# led_and_button.net
KiCad netlist of a schematic drawn in Altium Designer
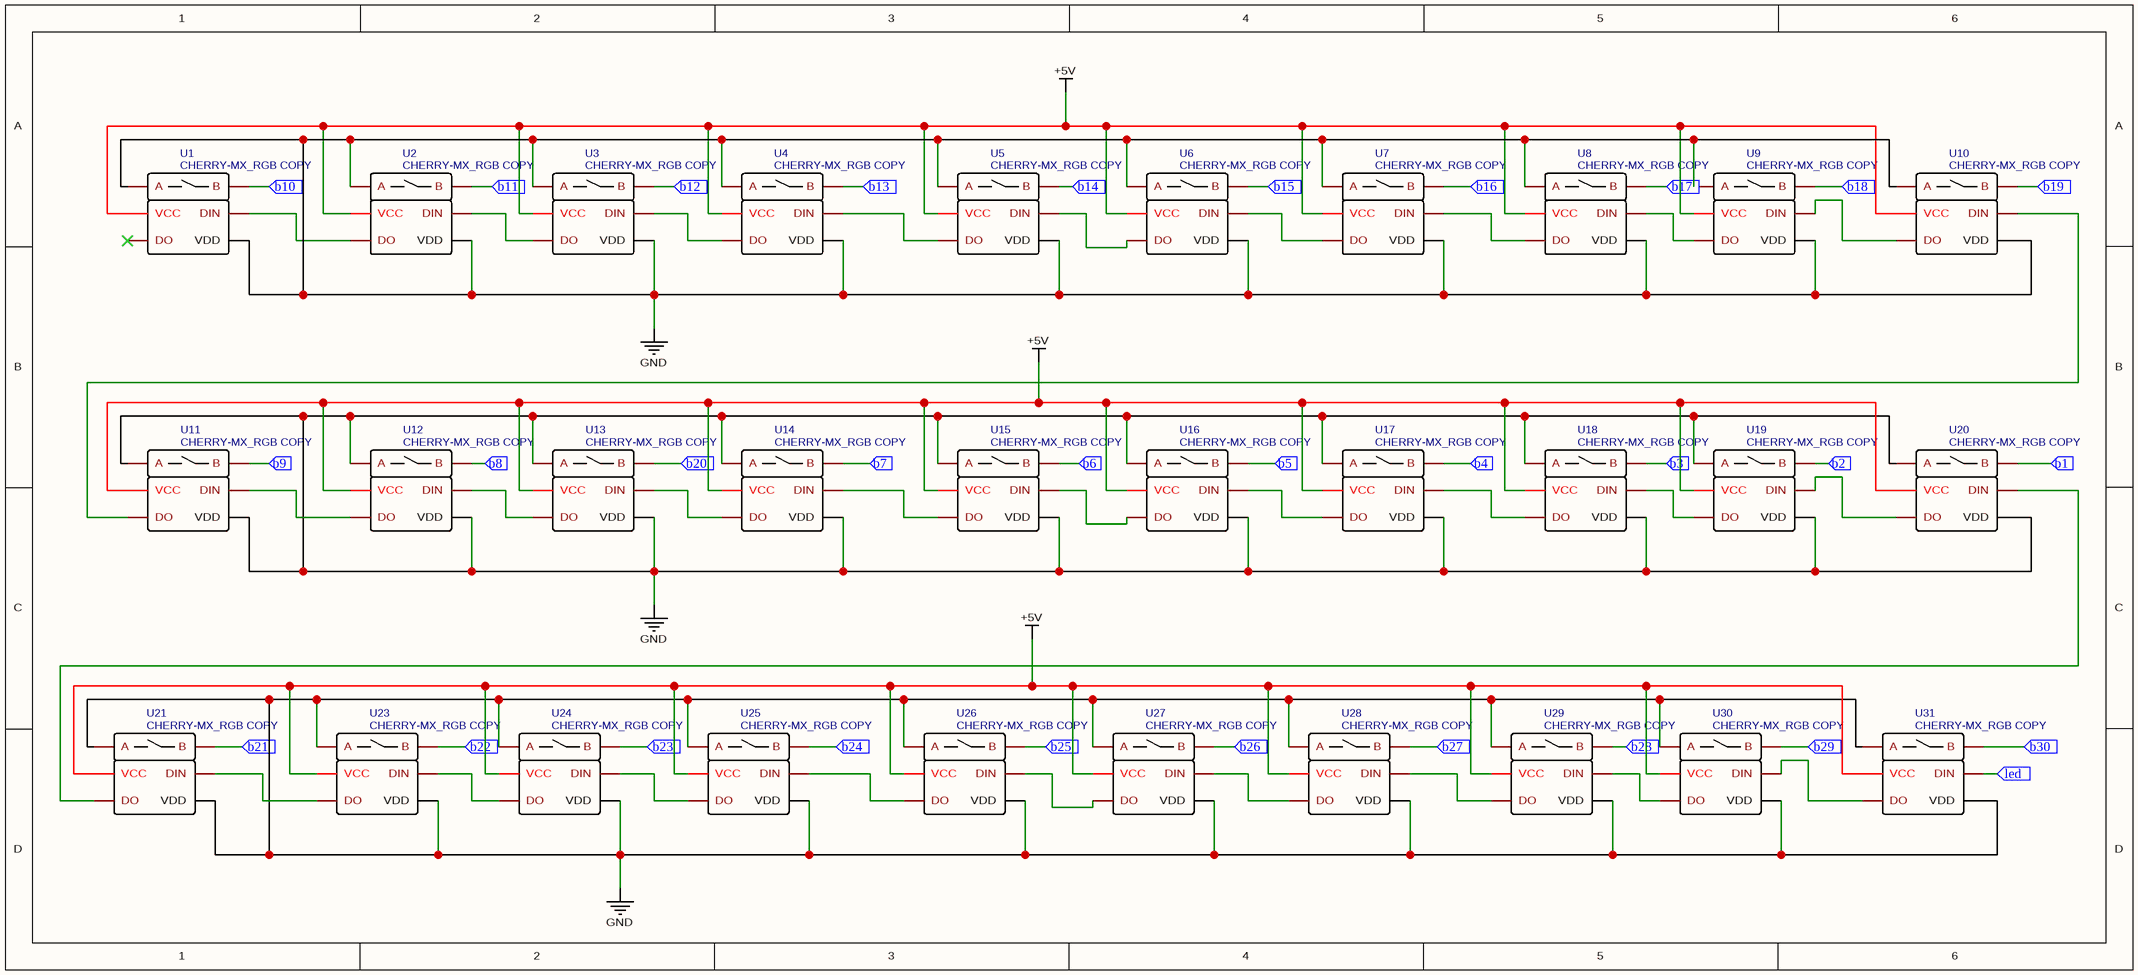
[diagram p0: led and button.schdoc]

(export (version "E")
  (design (tool "Eeschema 10.0.6"))
  (components
    (comp (ref "U1")
      (value "CHERRY-MX_RGB COPY")
      (fields (field (name "CONTRIBUTOR") "unrealin01"))
      (libsource (lib "altium-import") (part "root_0_CHERRY-MX_RGB COPY_"))
    )
    (comp (ref "U2")
      (value "CHERRY-MX_RGB COPY")
      (fields (field (name "CONTRIBUTOR") "unrealin01"))
      (libsource (lib "altium-import") (part "root_0_CHERRY-MX_RGB COPY_"))
    )
    (comp (ref "U3")
      (value "CHERRY-MX_RGB COPY")
      (fields (field (name "CONTRIBUTOR") "unrealin01"))
      (libsource (lib "altium-import") (part "root_0_CHERRY-MX_RGB COPY_"))
    )
    (comp (ref "U4")
      (value "CHERRY-MX_RGB COPY")
      (fields (field (name "CONTRIBUTOR") "unrealin01"))
      (libsource (lib "altium-import") (part "root_0_CHERRY-MX_RGB COPY_"))
    )
    (comp (ref "U5")
      (value "CHERRY-MX_RGB COPY")
      (fields (field (name "CONTRIBUTOR") "unrealin01"))
      (libsource (lib "altium-import") (part "root_0_CHERRY-MX_RGB COPY_"))
    )
    (comp (ref "U6")
      (value "CHERRY-MX_RGB COPY")
      (fields (field (name "CONTRIBUTOR") "unrealin01"))
      (libsource (lib "altium-import") (part "root_0_CHERRY-MX_RGB COPY_"))
    )
    (comp (ref "U7")
      (value "CHERRY-MX_RGB COPY")
      (fields (field (name "CONTRIBUTOR") "unrealin01"))
      (libsource (lib "altium-import") (part "root_0_CHERRY-MX_RGB COPY_"))
    )
    (comp (ref "U8")
      (value "CHERRY-MX_RGB COPY")
      (fields (field (name "CONTRIBUTOR") "unrealin01"))
      (libsource (lib "altium-import") (part "root_0_CHERRY-MX_RGB COPY_"))
    )
    (comp (ref "U9")
      (value "CHERRY-MX_RGB COPY")
      (fields (field (name "CONTRIBUTOR") "unrealin01"))
      (libsource (lib "altium-import") (part "root_0_CHERRY-MX_RGB COPY_"))
    )
    (comp (ref "U10")
      (value "CHERRY-MX_RGB COPY")
      (fields (field (name "CONTRIBUTOR") "unrealin01"))
      (libsource (lib "altium-import") (part "root_0_CHERRY-MX_RGB COPY_"))
    )
    (comp (ref "U11")
      (value "CHERRY-MX_RGB COPY")
      (fields (field (name "CONTRIBUTOR") "unrealin01"))
      (libsource (lib "altium-import") (part "root_0_CHERRY-MX_RGB COPY_"))
    )
    (comp (ref "U12")
      (value "CHERRY-MX_RGB COPY")
      (fields (field (name "CONTRIBUTOR") "unrealin01"))
      (libsource (lib "altium-import") (part "root_0_CHERRY-MX_RGB COPY_"))
    )
    (comp (ref "U13")
      (value "CHERRY-MX_RGB COPY")
      (fields (field (name "CONTRIBUTOR") "unrealin01"))
      (libsource (lib "altium-import") (part "root_0_CHERRY-MX_RGB COPY_"))
    )
    (comp (ref "U14")
      (value "CHERRY-MX_RGB COPY")
      (fields (field (name "CONTRIBUTOR") "unrealin01"))
      (libsource (lib "altium-import") (part "root_0_CHERRY-MX_RGB COPY_"))
    )
    (comp (ref "U15")
      (value "CHERRY-MX_RGB COPY")
      (fields (field (name "CONTRIBUTOR") "unrealin01"))
      (libsource (lib "altium-import") (part "root_0_CHERRY-MX_RGB COPY_"))
    )
    (comp (ref "U16")
      (value "CHERRY-MX_RGB COPY")
      (fields (field (name "CONTRIBUTOR") "unrealin01"))
      (libsource (lib "altium-import") (part "root_0_CHERRY-MX_RGB COPY_"))
    )
    (comp (ref "U17")
      (value "CHERRY-MX_RGB COPY")
      (fields (field (name "CONTRIBUTOR") "unrealin01"))
      (libsource (lib "altium-import") (part "root_0_CHERRY-MX_RGB COPY_"))
    )
    (comp (ref "U18")
      (value "CHERRY-MX_RGB COPY")
      (fields (field (name "CONTRIBUTOR") "unrealin01"))
      (libsource (lib "altium-import") (part "root_0_CHERRY-MX_RGB COPY_"))
    )
    (comp (ref "U19")
      (value "CHERRY-MX_RGB COPY")
      (fields (field (name "CONTRIBUTOR") "unrealin01"))
      (libsource (lib "altium-import") (part "root_0_CHERRY-MX_RGB COPY_"))
    )
    (comp (ref "U20")
      (value "CHERRY-MX_RGB COPY")
      (fields (field (name "CONTRIBUTOR") "unrealin01"))
      (libsource (lib "altium-import") (part "root_0_CHERRY-MX_RGB COPY_"))
    )
    (comp (ref "U21")
      (value "CHERRY-MX_RGB COPY")
      (fields (field (name "CONTRIBUTOR") "unrealin01"))
      (libsource (lib "altium-import") (part "root_0_CHERRY-MX_RGB COPY_"))
    )
    (comp (ref "U23")
      (value "CHERRY-MX_RGB COPY")
      (fields (field (name "CONTRIBUTOR") "unrealin01"))
      (libsource (lib "altium-import") (part "root_0_CHERRY-MX_RGB COPY_"))
    )
    (comp (ref "U24")
      (value "CHERRY-MX_RGB COPY")
      (fields (field (name "CONTRIBUTOR") "unrealin01"))
      (libsource (lib "altium-import") (part "root_0_CHERRY-MX_RGB COPY_"))
    )
    (comp (ref "U25")
      (value "CHERRY-MX_RGB COPY")
      (fields (field (name "CONTRIBUTOR") "unrealin01"))
      (libsource (lib "altium-import") (part "root_0_CHERRY-MX_RGB COPY_"))
    )
    (comp (ref "U26")
      (value "CHERRY-MX_RGB COPY")
      (fields (field (name "CONTRIBUTOR") "unrealin01"))
      (libsource (lib "altium-import") (part "root_0_CHERRY-MX_RGB COPY_"))
    )
    (comp (ref "U27")
      (value "CHERRY-MX_RGB COPY")
      (fields (field (name "CONTRIBUTOR") "unrealin01"))
      (libsource (lib "altium-import") (part "root_0_CHERRY-MX_RGB COPY_"))
    )
    (comp (ref "U28")
      (value "CHERRY-MX_RGB COPY")
      (fields (field (name "CONTRIBUTOR") "unrealin01"))
      (libsource (lib "altium-import") (part "root_0_CHERRY-MX_RGB COPY_"))
    )
    (comp (ref "U29")
      (value "CHERRY-MX_RGB COPY")
      (fields (field (name "CONTRIBUTOR") "unrealin01"))
      (libsource (lib "altium-import") (part "root_0_CHERRY-MX_RGB COPY_"))
    )
    (comp (ref "U30")
      (value "CHERRY-MX_RGB COPY")
      (fields (field (name "CONTRIBUTOR") "unrealin01"))
      (libsource (lib "altium-import") (part "root_0_CHERRY-MX_RGB COPY_"))
    )
    (comp (ref "U31")
      (value "CHERRY-MX_RGB COPY")
      (fields (field (name "CONTRIBUTOR") "unrealin01"))
      (libsource (lib "altium-import") (part "root_0_CHERRY-MX_RGB COPY_"))
    )
  )
  (nets
    (net (code "1") (name "+5V") (class "Default")
      (node (ref "U1") (pin "3") (pinfunction "VCC_3") (pintype "passive"))
      (node (ref "U10") (pin "3") (pinfunction "VCC_3") (pintype "passive"))
      (node (ref "U11") (pin "3") (pinfunction "VCC_3") (pintype "passive"))
      (node (ref "U12") (pin "3") (pinfunction "VCC_3") (pintype "passive"))
      (node (ref "U13") (pin "3") (pinfunction "VCC_3") (pintype "passive"))
      (node (ref "U14") (pin "3") (pinfunction "VCC_3") (pintype "passive"))
      (node (ref "U15") (pin "3") (pinfunction "VCC_3") (pintype "passive"))
      (node (ref "U16") (pin "3") (pinfunction "VCC_3") (pintype "passive"))
      (node (ref "U17") (pin "3") (pinfunction "VCC_3") (pintype "passive"))
      (node (ref "U18") (pin "3") (pinfunction "VCC_3") (pintype "passive"))
      (node (ref "U19") (pin "3") (pinfunction "VCC_3") (pintype "passive"))
      (node (ref "U2") (pin "3") (pinfunction "VCC_3") (pintype "passive"))
      (node (ref "U20") (pin "3") (pinfunction "VCC_3") (pintype "passive"))
      (node (ref "U21") (pin "3") (pinfunction "VCC_3") (pintype "passive"))
      (node (ref "U23") (pin "3") (pinfunction "VCC_3") (pintype "passive"))
      (node (ref "U24") (pin "3") (pinfunction "VCC_3") (pintype "passive"))
      (node (ref "U25") (pin "3") (pinfunction "VCC_3") (pintype "passive"))
      (node (ref "U26") (pin "3") (pinfunction "VCC_3") (pintype "passive"))
      (node (ref "U27") (pin "3") (pinfunction "VCC_3") (pintype "passive"))
      (node (ref "U28") (pin "3") (pinfunction "VCC_3") (pintype "passive"))
      (node (ref "U29") (pin "3") (pinfunction "VCC_3") (pintype "passive"))
      (node (ref "U3") (pin "3") (pinfunction "VCC_3") (pintype "passive"))
      (node (ref "U30") (pin "3") (pinfunction "VCC_3") (pintype "passive"))
      (node (ref "U31") (pin "3") (pinfunction "VCC_3") (pintype "passive"))
      (node (ref "U4") (pin "3") (pinfunction "VCC_3") (pintype "passive"))
      (node (ref "U5") (pin "3") (pinfunction "VCC_3") (pintype "passive"))
      (node (ref "U6") (pin "3") (pinfunction "VCC_3") (pintype "passive"))
      (node (ref "U7") (pin "3") (pinfunction "VCC_3") (pintype "passive"))
      (node (ref "U8") (pin "3") (pinfunction "VCC_3") (pintype "passive"))
      (node (ref "U9") (pin "3") (pinfunction "VCC_3") (pintype "passive"))
    )
    (net (code "2") (name "/b1") (class "Default")
      (node (ref "U20") (pin "2") (pinfunction "B_2") (pintype "passive"))
    )
    (net (code "3") (name "/b2") (class "Default")
      (node (ref "U19") (pin "2") (pinfunction "B_2") (pintype "passive"))
    )
    (net (code "4") (name "/b3") (class "Default")
      (node (ref "U18") (pin "2") (pinfunction "B_2") (pintype "passive"))
    )
    (net (code "5") (name "/b4") (class "Default")
      (node (ref "U17") (pin "2") (pinfunction "B_2") (pintype "passive"))
    )
    (net (code "6") (name "/b5") (class "Default")
      (node (ref "U16") (pin "2") (pinfunction "B_2") (pintype "passive"))
    )
    (net (code "7") (name "/b6") (class "Default")
      (node (ref "U15") (pin "2") (pinfunction "B_2") (pintype "passive"))
    )
    (net (code "8") (name "/b7") (class "Default")
      (node (ref "U14") (pin "2") (pinfunction "B_2") (pintype "passive"))
    )
    (net (code "9") (name "/b8") (class "Default")
      (node (ref "U12") (pin "2") (pinfunction "B_2") (pintype "passive"))
    )
    (net (code "10") (name "/b9") (class "Default")
      (node (ref "U11") (pin "2") (pinfunction "B_2") (pintype "passive"))
    )
    (net (code "11") (name "/b10") (class "Default")
      (node (ref "U1") (pin "2") (pinfunction "B_2") (pintype "passive"))
    )
    (net (code "12") (name "/b11") (class "Default")
      (node (ref "U2") (pin "2") (pinfunction "B_2") (pintype "passive"))
    )
    (net (code "13") (name "/b12") (class "Default")
      (node (ref "U3") (pin "2") (pinfunction "B_2") (pintype "passive"))
    )
    (net (code "14") (name "/b13") (class "Default")
      (node (ref "U4") (pin "2") (pinfunction "B_2") (pintype "passive"))
    )
    (net (code "15") (name "/b14") (class "Default")
      (node (ref "U5") (pin "2") (pinfunction "B_2") (pintype "passive"))
    )
    (net (code "16") (name "/b15") (class "Default")
      (node (ref "U6") (pin "2") (pinfunction "B_2") (pintype "passive"))
    )
    (net (code "17") (name "/b16") (class "Default")
      (node (ref "U7") (pin "2") (pinfunction "B_2") (pintype "passive"))
    )
    (net (code "18") (name "/b17") (class "Default")
      (node (ref "U8") (pin "2") (pinfunction "B_2") (pintype "passive"))
    )
    (net (code "19") (name "/b18") (class "Default")
      (node (ref "U9") (pin "2") (pinfunction "B_2") (pintype "passive"))
    )
    (net (code "20") (name "/b19") (class "Default")
      (node (ref "U10") (pin "2") (pinfunction "B_2") (pintype "passive"))
    )
    (net (code "21") (name "/b20") (class "Default")
      (node (ref "U13") (pin "2") (pinfunction "B_2") (pintype "passive"))
    )
    (net (code "22") (name "/b21") (class "Default")
      (node (ref "U21") (pin "2") (pinfunction "B_2") (pintype "passive"))
    )
    (net (code "23") (name "/b22") (class "Default")
      (node (ref "U23") (pin "2") (pinfunction "B_2") (pintype "passive"))
    )
    (net (code "24") (name "/b23") (class "Default")
      (node (ref "U24") (pin "2") (pinfunction "B_2") (pintype "passive"))
    )
    (net (code "25") (name "/b24") (class "Default")
      (node (ref "U25") (pin "2") (pinfunction "B_2") (pintype "passive"))
    )
    (net (code "26") (name "/b25") (class "Default")
      (node (ref "U26") (pin "2") (pinfunction "B_2") (pintype "passive"))
    )
    (net (code "27") (name "/b26") (class "Default")
      (node (ref "U27") (pin "2") (pinfunction "B_2") (pintype "passive"))
    )
    (net (code "28") (name "/b27") (class "Default")
      (node (ref "U28") (pin "2") (pinfunction "B_2") (pintype "passive"))
    )
    (net (code "29") (name "/b28") (class "Default")
      (node (ref "U29") (pin "2") (pinfunction "B_2") (pintype "passive"))
    )
    (net (code "30") (name "/b29") (class "Default")
      (node (ref "U30") (pin "2") (pinfunction "B_2") (pintype "passive"))
    )
    (net (code "31") (name "/b30") (class "Default")
      (node (ref "U31") (pin "2") (pinfunction "B_2") (pintype "passive"))
    )
    (net (code "32") (name "/led") (class "Default")
      (node (ref "U31") (pin "6") (pinfunction "DIN_6") (pintype "passive"))
    )
    (net (code "33") (name "GND") (class "Default")
      (node (ref "U1") (pin "1") (pinfunction "A_1") (pintype "passive"))
      (node (ref "U1") (pin "5") (pinfunction "VDD_5") (pintype "passive"))
      (node (ref "U10") (pin "1") (pinfunction "A_1") (pintype "passive"))
      (node (ref "U10") (pin "5") (pinfunction "VDD_5") (pintype "passive"))
      (node (ref "U11") (pin "1") (pinfunction "A_1") (pintype "passive"))
      (node (ref "U11") (pin "5") (pinfunction "VDD_5") (pintype "passive"))
      (node (ref "U12") (pin "1") (pinfunction "A_1") (pintype "passive"))
      (node (ref "U12") (pin "5") (pinfunction "VDD_5") (pintype "passive"))
      (node (ref "U13") (pin "1") (pinfunction "A_1") (pintype "passive"))
      (node (ref "U13") (pin "5") (pinfunction "VDD_5") (pintype "passive"))
      (node (ref "U14") (pin "1") (pinfunction "A_1") (pintype "passive"))
      (node (ref "U14") (pin "5") (pinfunction "VDD_5") (pintype "passive"))
      (node (ref "U15") (pin "1") (pinfunction "A_1") (pintype "passive"))
      (node (ref "U15") (pin "5") (pinfunction "VDD_5") (pintype "passive"))
      (node (ref "U16") (pin "1") (pinfunction "A_1") (pintype "passive"))
      (node (ref "U16") (pin "5") (pinfunction "VDD_5") (pintype "passive"))
      (node (ref "U17") (pin "1") (pinfunction "A_1") (pintype "passive"))
      (node (ref "U17") (pin "5") (pinfunction "VDD_5") (pintype "passive"))
      (node (ref "U18") (pin "1") (pinfunction "A_1") (pintype "passive"))
      (node (ref "U18") (pin "5") (pinfunction "VDD_5") (pintype "passive"))
      (node (ref "U19") (pin "1") (pinfunction "A_1") (pintype "passive"))
      (node (ref "U19") (pin "5") (pinfunction "VDD_5") (pintype "passive"))
      (node (ref "U2") (pin "1") (pinfunction "A_1") (pintype "passive"))
      (node (ref "U2") (pin "5") (pinfunction "VDD_5") (pintype "passive"))
      (node (ref "U20") (pin "1") (pinfunction "A_1") (pintype "passive"))
      (node (ref "U20") (pin "5") (pinfunction "VDD_5") (pintype "passive"))
      (node (ref "U21") (pin "1") (pinfunction "A_1") (pintype "passive"))
      (node (ref "U21") (pin "5") (pinfunction "VDD_5") (pintype "passive"))
      (node (ref "U23") (pin "1") (pinfunction "A_1") (pintype "passive"))
      (node (ref "U23") (pin "5") (pinfunction "VDD_5") (pintype "passive"))
      (node (ref "U24") (pin "1") (pinfunction "A_1") (pintype "passive"))
      (node (ref "U24") (pin "5") (pinfunction "VDD_5") (pintype "passive"))
      (node (ref "U25") (pin "1") (pinfunction "A_1") (pintype "passive"))
      (node (ref "U25") (pin "5") (pinfunction "VDD_5") (pintype "passive"))
      (node (ref "U26") (pin "1") (pinfunction "A_1") (pintype "passive"))
      (node (ref "U26") (pin "5") (pinfunction "VDD_5") (pintype "passive"))
      (node (ref "U27") (pin "1") (pinfunction "A_1") (pintype "passive"))
      (node (ref "U27") (pin "5") (pinfunction "VDD_5") (pintype "passive"))
      (node (ref "U28") (pin "1") (pinfunction "A_1") (pintype "passive"))
      (node (ref "U28") (pin "5") (pinfunction "VDD_5") (pintype "passive"))
      (node (ref "U29") (pin "1") (pinfunction "A_1") (pintype "passive"))
      (node (ref "U29") (pin "5") (pinfunction "VDD_5") (pintype "passive"))
      (node (ref "U3") (pin "1") (pinfunction "A_1") (pintype "passive"))
      (node (ref "U3") (pin "5") (pinfunction "VDD_5") (pintype "passive"))
      (node (ref "U30") (pin "1") (pinfunction "A_1") (pintype "passive"))
      (node (ref "U30") (pin "5") (pinfunction "VDD_5") (pintype "passive"))
      (node (ref "U31") (pin "1") (pinfunction "A_1") (pintype "passive"))
      (node (ref "U31") (pin "5") (pinfunction "VDD_5") (pintype "passive"))
      (node (ref "U4") (pin "1") (pinfunction "A_1") (pintype "passive"))
      (node (ref "U4") (pin "5") (pinfunction "VDD_5") (pintype "passive"))
      (node (ref "U5") (pin "1") (pinfunction "A_1") (pintype "passive"))
      (node (ref "U5") (pin "5") (pinfunction "VDD_5") (pintype "passive"))
      (node (ref "U6") (pin "1") (pinfunction "A_1") (pintype "passive"))
      (node (ref "U6") (pin "5") (pinfunction "VDD_5") (pintype "passive"))
      (node (ref "U7") (pin "1") (pinfunction "A_1") (pintype "passive"))
      (node (ref "U7") (pin "5") (pinfunction "VDD_5") (pintype "passive"))
      (node (ref "U8") (pin "1") (pinfunction "A_1") (pintype "passive"))
      (node (ref "U8") (pin "5") (pinfunction "VDD_5") (pintype "passive"))
      (node (ref "U9") (pin "1") (pinfunction "A_1") (pintype "passive"))
      (node (ref "U9") (pin "5") (pinfunction "VDD_5") (pintype "passive"))
    )
    (net (code "34") (name "Net-(U1-DIN)") (class "Default")
      (node (ref "U1") (pin "6") (pinfunction "DIN_6") (pintype "passive"))
      (node (ref "U2") (pin "4") (pinfunction "DO_4") (pintype "passive"))
    )
    (net (code "35") (name "Net-(U2-DIN)") (class "Default")
      (node (ref "U2") (pin "6") (pinfunction "DIN_6") (pintype "passive"))
      (node (ref "U3") (pin "4") (pinfunction "DO_4") (pintype "passive"))
    )
    (net (code "36") (name "Net-(U3-DIN)") (class "Default")
      (node (ref "U3") (pin "6") (pinfunction "DIN_6") (pintype "passive"))
      (node (ref "U4") (pin "4") (pinfunction "DO_4") (pintype "passive"))
    )
    (net (code "37") (name "Net-(U4-DIN)") (class "Default")
      (node (ref "U4") (pin "6") (pinfunction "DIN_6") (pintype "passive"))
      (node (ref "U5") (pin "4") (pinfunction "DO_4") (pintype "passive"))
    )
    (net (code "38") (name "Net-(U5-DIN)") (class "Default")
      (node (ref "U5") (pin "6") (pinfunction "DIN_6") (pintype "passive"))
      (node (ref "U6") (pin "4") (pinfunction "DO_4") (pintype "passive"))
    )
    (net (code "39") (name "Net-(U6-DIN)") (class "Default")
      (node (ref "U6") (pin "6") (pinfunction "DIN_6") (pintype "passive"))
      (node (ref "U7") (pin "4") (pinfunction "DO_4") (pintype "passive"))
    )
    (net (code "40") (name "Net-(U7-DIN)") (class "Default")
      (node (ref "U7") (pin "6") (pinfunction "DIN_6") (pintype "passive"))
      (node (ref "U8") (pin "4") (pinfunction "DO_4") (pintype "passive"))
    )
    (net (code "41") (name "Net-(U8-DIN)") (class "Default")
      (node (ref "U8") (pin "6") (pinfunction "DIN_6") (pintype "passive"))
      (node (ref "U9") (pin "4") (pinfunction "DO_4") (pintype "passive"))
    )
    (net (code "42") (name "Net-(U10-DIN)") (class "Default")
      (node (ref "U10") (pin "6") (pinfunction "DIN_6") (pintype "passive"))
      (node (ref "U11") (pin "4") (pinfunction "DO_4") (pintype "passive"))
    )
    (net (code "43") (name "Net-(U10-DO)") (class "Default")
      (node (ref "U10") (pin "4") (pinfunction "DO_4") (pintype "passive"))
      (node (ref "U9") (pin "6") (pinfunction "DIN_6") (pintype "passive"))
    )
    (net (code "44") (name "Net-(U11-DIN)") (class "Default")
      (node (ref "U11") (pin "6") (pinfunction "DIN_6") (pintype "passive"))
      (node (ref "U12") (pin "4") (pinfunction "DO_4") (pintype "passive"))
    )
    (net (code "45") (name "Net-(U12-DIN)") (class "Default")
      (node (ref "U12") (pin "6") (pinfunction "DIN_6") (pintype "passive"))
      (node (ref "U13") (pin "4") (pinfunction "DO_4") (pintype "passive"))
    )
    (net (code "46") (name "Net-(U13-DIN)") (class "Default")
      (node (ref "U13") (pin "6") (pinfunction "DIN_6") (pintype "passive"))
      (node (ref "U14") (pin "4") (pinfunction "DO_4") (pintype "passive"))
    )
    (net (code "47") (name "Net-(U14-DIN)") (class "Default")
      (node (ref "U14") (pin "6") (pinfunction "DIN_6") (pintype "passive"))
      (node (ref "U15") (pin "4") (pinfunction "DO_4") (pintype "passive"))
    )
    (net (code "48") (name "Net-(U15-DIN)") (class "Default")
      (node (ref "U15") (pin "6") (pinfunction "DIN_6") (pintype "passive"))
      (node (ref "U16") (pin "4") (pinfunction "DO_4") (pintype "passive"))
    )
    (net (code "49") (name "Net-(U16-DIN)") (class "Default")
      (node (ref "U16") (pin "6") (pinfunction "DIN_6") (pintype "passive"))
      (node (ref "U17") (pin "4") (pinfunction "DO_4") (pintype "passive"))
    )
    (net (code "50") (name "Net-(U17-DIN)") (class "Default")
      (node (ref "U17") (pin "6") (pinfunction "DIN_6") (pintype "passive"))
      (node (ref "U18") (pin "4") (pinfunction "DO_4") (pintype "passive"))
    )
    (net (code "51") (name "Net-(U18-DIN)") (class "Default")
      (node (ref "U18") (pin "6") (pinfunction "DIN_6") (pintype "passive"))
      (node (ref "U19") (pin "4") (pinfunction "DO_4") (pintype "passive"))
    )
    (net (code "52") (name "Net-(U19-DIN)") (class "Default")
      (node (ref "U19") (pin "6") (pinfunction "DIN_6") (pintype "passive"))
      (node (ref "U20") (pin "4") (pinfunction "DO_4") (pintype "passive"))
    )
    (net (code "53") (name "Net-(U20-DIN)") (class "Default")
      (node (ref "U20") (pin "6") (pinfunction "DIN_6") (pintype "passive"))
      (node (ref "U21") (pin "4") (pinfunction "DO_4") (pintype "passive"))
    )
    (net (code "54") (name "Net-(U21-DIN)") (class "Default")
      (node (ref "U21") (pin "6") (pinfunction "DIN_6") (pintype "passive"))
      (node (ref "U23") (pin "4") (pinfunction "DO_4") (pintype "passive"))
    )
    (net (code "55") (name "Net-(U23-DIN)") (class "Default")
      (node (ref "U23") (pin "6") (pinfunction "DIN_6") (pintype "passive"))
      (node (ref "U24") (pin "4") (pinfunction "DO_4") (pintype "passive"))
    )
    (net (code "56") (name "Net-(U24-DIN)") (class "Default")
      (node (ref "U24") (pin "6") (pinfunction "DIN_6") (pintype "passive"))
      (node (ref "U25") (pin "4") (pinfunction "DO_4") (pintype "passive"))
    )
    (net (code "57") (name "Net-(U25-DIN)") (class "Default")
      (node (ref "U25") (pin "6") (pinfunction "DIN_6") (pintype "passive"))
      (node (ref "U26") (pin "4") (pinfunction "DO_4") (pintype "passive"))
    )
    (net (code "58") (name "Net-(U26-DIN)") (class "Default")
      (node (ref "U26") (pin "6") (pinfunction "DIN_6") (pintype "passive"))
      (node (ref "U27") (pin "4") (pinfunction "DO_4") (pintype "passive"))
    )
    (net (code "59") (name "Net-(U27-DIN)") (class "Default")
      (node (ref "U27") (pin "6") (pinfunction "DIN_6") (pintype "passive"))
      (node (ref "U28") (pin "4") (pinfunction "DO_4") (pintype "passive"))
    )
    (net (code "60") (name "Net-(U28-DIN)") (class "Default")
      (node (ref "U28") (pin "6") (pinfunction "DIN_6") (pintype "passive"))
      (node (ref "U29") (pin "4") (pinfunction "DO_4") (pintype "passive"))
    )
    (net (code "61") (name "Net-(U29-DIN)") (class "Default")
      (node (ref "U29") (pin "6") (pinfunction "DIN_6") (pintype "passive"))
      (node (ref "U30") (pin "4") (pinfunction "DO_4") (pintype "passive"))
    )
    (net (code "62") (name "Net-(U30-DIN)") (class "Default")
      (node (ref "U30") (pin "6") (pinfunction "DIN_6") (pintype "passive"))
      (node (ref "U31") (pin "4") (pinfunction "DO_4") (pintype "passive"))
    )
    (net (code "63") (name "unconnected-(U1-DO-Pad4)") (class "Default")
      (node (ref "U1") (pin "4") (pinfunction "DO_4") (pintype "passive+no_connect"))
    )
  )
)
